# RECEIVER.net
KiCad netlist of a schematic drawn in Altium Designer
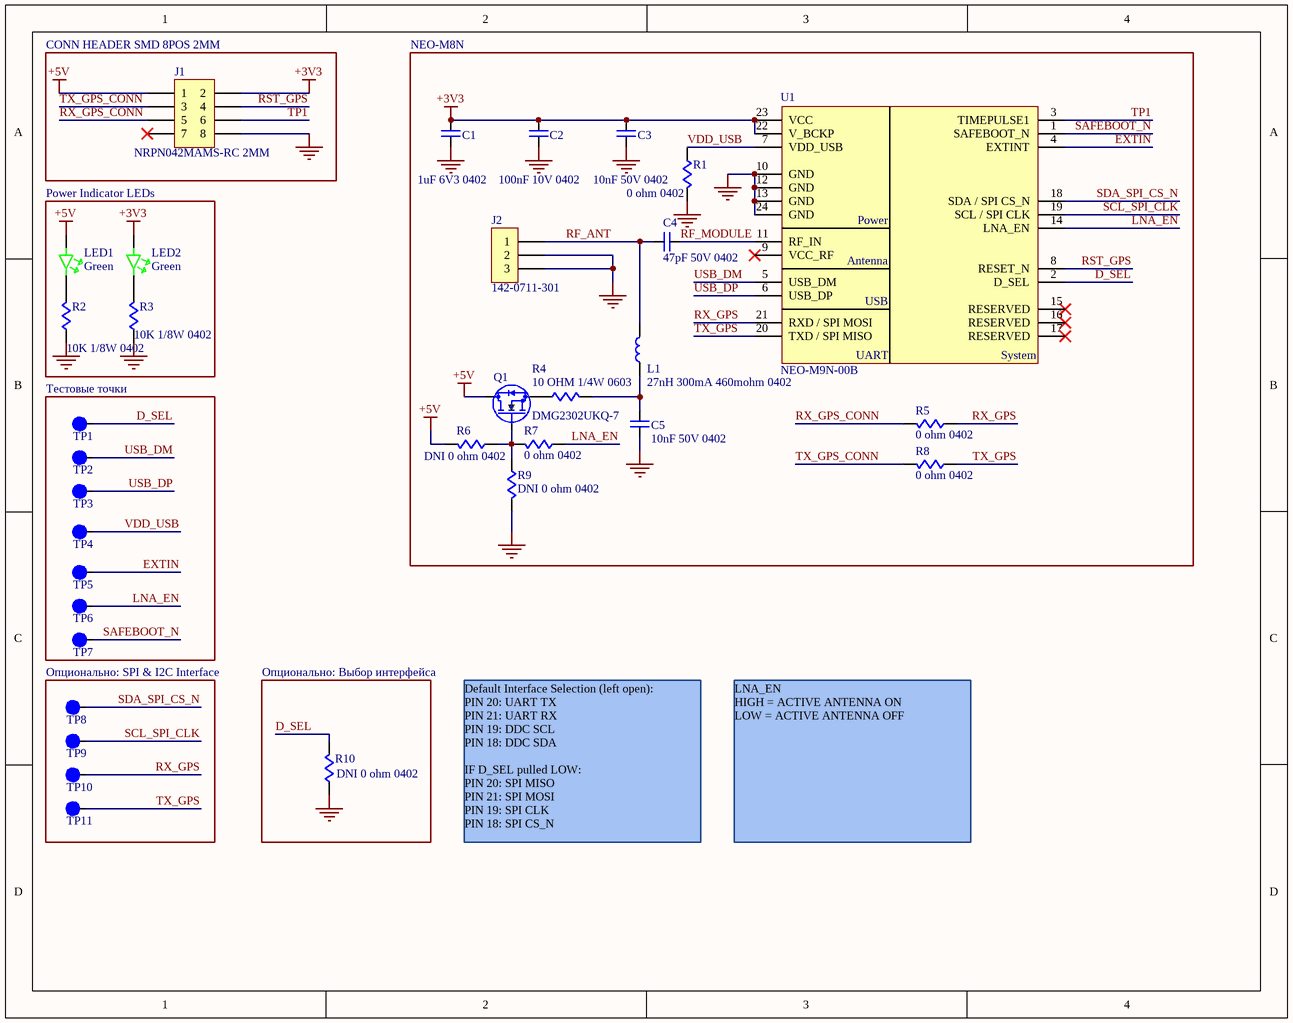
[diagram p0: RECEIVER.SchDoc]

(export (version "E")
  (design (tool "Eeschema 10.0.6"))
  (components
    (comp (ref "C1")
      (value "1uF 6V3 0402")
      (footprint "c0402")
      (description "0402 1 uF 6.3 V ±10% Tolerance X7R Multilayer Ceramic Capacitor")
      (fields
        (field (name "MANUFACTURER") "Murata")
        (field (name "MANUFACTURER PART NUMBER") "GRM155R70J105KA12J")
      )
      (libsource (lib "MyLibrary") (part "CAP CER 1UF 6.3V X7R 0402"))
    )
    (comp (ref "C2")
      (value "100nF 10V 0402")
      (footprint "c0402")
      (description "CL05 Series 0.1 uF 10 V ±10 % Tolerance X7R SMT Multilayer Ceramic Capacitor")
      (fields
        (field (name "MANUFACTURER") "Samsung")
        (field (name "MANUFACTURER PART NUMBER") "CL05B104KP5NNNC")
      )
      (libsource (lib "MyLibrary") (part "CAP CER 0.1UF 10V X7R 0402"))
    )
    (comp (ref "C3")
      (value "10nF 50V 0402")
      (footprint "c0402")
      (description "CAP CER 10000PF 50V X7R 0402")
      (fields
        (field (name "MANUFACTURER") "Murata")
        (field (name "MANUFACTURER PART NUMBER") "GCM155R71H103KA55D")
      )
      (libsource (lib "MyLibrary") (part "CAP CER 10000PF 50V X7R 0402"))
    )
    (comp (ref "C4")
      (value "47pF 50V 0402")
      (footprint "c0402")
      (description "0402 47 pF 50 V ±5 % Tolerance NP0 SMT Multilayer Ceramic Capacitor")
      (fields
        (field (name "MANUFACTURER") "Yageo")
        (field (name "MANUFACTURER PART NUMBER") "CC0402JRNPO9BN470")
      )
      (libsource (lib "MyLibrary") (part "CAP CER 47PF 50V C0G/NPO 0402"))
    )
    (comp (ref "C5")
      (value "10nF 50V 0402")
      (footprint "c0402")
      (description "CAP CER 10000PF 50V X7R 0402")
      (fields
        (field (name "MANUFACTURER") "Murata")
        (field (name "MANUFACTURER PART NUMBER") "GCM155R71H103KA55D")
      )
      (libsource (lib "MyLibrary") (part "CAP CER 10000PF 50V X7R 0402"))
    )
    (comp (ref "J1")
      (value "NRPN042MAMS-RC 2MM")
      (footprint "CONN_NRPN042MAMS-RC")
      (description "Dual Row 8 Position 2 mm Pitch Surface Mount Header")
      (fields
        (field (name "MANUFACTURER") "Sullins")
        (field (name "MANUFACTURER PART NUMBER") "NRPN042MAMS-RC")
      )
      (libsource (lib "MyLibrary") (part "CONN_NRPN042MAMS-RC"))
    )
    (comp (ref "J2")
      (value "142-0711-301")
      (footprint "CONN_131-3711-301")
      (description "Rf Coaxial Board Mount Connector")
      (fields
        (field (name "MANUFACTURER") "Bel Cinch")
        (field (name "MANUFACTURER PART NUMBER") "131-3711-301")
      )
      (libsource (lib "MyLibrary") (part "CONN_131-3711-301"))
    )
    (comp (ref "L1")
      (value "27nH 300mA 460mohm 0402")
      (footprint "L0402")
      (description "Inductor RF Chip Multi-Layer 27nH 5% 100MHz 8Q-Factor Air 300mA 460mOhm DCR 0402 Paper T/R")
      (fields
        (field (name "MANUFACTURER") "Murata")
        (field (name "MANUFACTURER PART NUMBER") "LQG15HS27NJ02D")
      )
      (libsource (lib "MyLibrary") (part "FIXED IND 27NH 350MA 460MOHM SMD"))
    )
    (comp (ref "LED1")
      (value "Green")
      (footprint "led0603")
      (description "LED High-Power Uni-Color Green 574nm 2-Pin Chip LED T/R")
      (fields
        (field (name "MANUFACTURER") "Vishay Lite-On")
        (field (name "MANUFACTURER PART NUMBER") "LTST-C190KGKT")
      )
      (libsource (lib "MyLibrary") (part "LED GREEN CLEAR CHIP SMD"))
    )
    (comp (ref "LED2")
      (value "Green")
      (footprint "led0603")
      (description "LED High-Power Uni-Color Green 574nm 2-Pin Chip LED T/R")
      (fields
        (field (name "MANUFACTURER") "Vishay Lite-On")
        (field (name "MANUFACTURER PART NUMBER") "LTST-C190KGKT")
      )
      (libsource (lib "MyLibrary") (part "LED GREEN CLEAR CHIP SMD"))
    )
    (comp (ref "Q1")
      (value "DMG2302UKQ-7")
      (footprint "SOT23")
      (description "N-Channel 20 V 2.8A (Ta) 660mW (Ta) Surface Mount SOT-23-3")
      (fields
        (field (name "MANUFACTURER") "Diodes")
        (field (name "COPYRIGHT") "Copyright (C) 2022 Ultra Librarian. All rights reserved.")
      )
      (libsource (lib "MyLibrary") (part "DMG2302UKQ-7"))
    )
    (comp (ref "R1")
      (value "0 ohm 0402")
      (footprint "r0402")
      (description "RES SMD 0 OHM JUMPER 1/16W 0402")
      (fields
        (field (name "MANUFACTURER") "Yageo")
        (field (name "MANUFACTURER PART NUMBER") "RC0402JR-070RL")
      )
      (libsource (lib "MyLibrary") (part "RES 0 OHM JUMPER 1/16W 0402"))
    )
    (comp (ref "R2")
      (value "10K 1/8W 0402")
      (footprint "r0402")
      (description "Res Thick Film 0402 10K Ohm 1% 0.125W(1/8W) ±100ppm/°C Pad SMD T/R")
      (fields
        (field (name "MANUFACTURER") "TE Connectivity")
        (field (name "MANUFACTURER PART NUMBER") "CRGP0402F10K")
      )
      (libsource (lib "MyLibrary") (part "RES 10K OHM 1% 1/8W 0402"))
    )
    (comp (ref "R3")
      (value "10K 1/8W 0402")
      (footprint "r0402")
      (description "Res Thick Film 0402 10K Ohm 1% 0.125W(1/8W) ±100ppm/°C Pad SMD T/R")
      (fields
        (field (name "MANUFACTURER") "TE Connectivity")
        (field (name "MANUFACTURER PART NUMBER") "CRGP0402F10K")
      )
      (libsource (lib "MyLibrary") (part "RES 10K OHM 1% 1/8W 0402"))
    )
    (comp (ref "R4")
      (value "10 OHM 1/4W 0603")
      (footprint "r0603")
      (description "Res Surge Chip Thick Film 0603 10 Ohm 1% 1/4W ±200ppm/°C Molded Paper T/R")
      (fields
        (field (name "MANUFACTURER") "Yageo")
        (field (name "MANUFACTURER PART NUMBER") "SR0603FR-7T10RL")
      )
      (libsource (lib "MyLibrary") (part "RES SMD 10 OHM 1% 1/4W 0603"))
    )
    (comp (ref "R5")
      (value "0 ohm 0402")
      (footprint "r0402")
      (description "RES SMD 0 OHM JUMPER 1/16W 0402")
      (fields
        (field (name "MANUFACTURER") "Yageo")
        (field (name "MANUFACTURER PART NUMBER") "RC0402JR-070RL")
      )
      (libsource (lib "MyLibrary") (part "RES 0 OHM JUMPER 1/16W 0402"))
    )
    (comp (ref "R6")
      (value "DNI 0 ohm 0402")
      (footprint "r0402")
      (description "RES SMD 0 OHM JUMPER 1/16W 0402")
      (fields
        (field (name "MANUFACTURER") "Yageo")
        (field (name "MANUFACTURER PART NUMBER") "RC0402JR-070RL")
      )
      (libsource (lib "MyLibrary") (part "RES 0 OHM JUMPER 1/16W 0402"))
    )
    (comp (ref "R7")
      (value "0 ohm 0402")
      (footprint "r0402")
      (description "RES SMD 0 OHM JUMPER 1/16W 0402")
      (fields
        (field (name "MANUFACTURER") "Yageo")
        (field (name "MANUFACTURER PART NUMBER") "RC0402JR-070RL")
      )
      (libsource (lib "MyLibrary") (part "RES 0 OHM JUMPER 1/16W 0402"))
    )
    (comp (ref "R8")
      (value "0 ohm 0402")
      (footprint "r0402")
      (description "RES SMD 0 OHM JUMPER 1/16W 0402")
      (fields
        (field (name "MANUFACTURER") "Yageo")
        (field (name "MANUFACTURER PART NUMBER") "RC0402JR-070RL")
      )
      (libsource (lib "MyLibrary") (part "RES 0 OHM JUMPER 1/16W 0402"))
    )
    (comp (ref "R9")
      (value "DNI 0 ohm 0402")
      (footprint "r0402")
      (description "RES SMD 0 OHM JUMPER 1/16W 0402")
      (fields
        (field (name "MANUFACTURER") "Yageo")
        (field (name "MANUFACTURER PART NUMBER") "RC0402JR-070RL")
      )
      (libsource (lib "MyLibrary") (part "RES 0 OHM JUMPER 1/16W 0402"))
    )
    (comp (ref "R10")
      (value "DNI 0 ohm 0402")
      (footprint "r0402")
      (description "RES SMD 0 OHM JUMPER 1/16W 0402")
      (fields
        (field (name "MANUFACTURER") "Yageo")
        (field (name "MANUFACTURER PART NUMBER") "RC0402JR-070RL")
      )
      (libsource (lib "MyLibrary") (part "RES 0 OHM JUMPER 1/16W 0402"))
    )
    (comp (ref "TP1")
      (value "1MM")
      (footprint "TP1MM")
      (description "Test Point 1MM diameter")
      (libsource (lib "MyLibrary") (part "TP_1MM"))
    )
    (comp (ref "TP2")
      (value "1MM")
      (footprint "TP1MM")
      (description "Test Point 1MM diameter")
      (libsource (lib "MyLibrary") (part "TP_1MM"))
    )
    (comp (ref "TP3")
      (value "1MM")
      (footprint "TP1MM")
      (description "Test Point 1MM diameter")
      (libsource (lib "MyLibrary") (part "TP_1MM"))
    )
    (comp (ref "TP4")
      (value "1MM")
      (footprint "TP1MM")
      (description "Test Point 1MM diameter")
      (libsource (lib "MyLibrary") (part "TP_1MM"))
    )
    (comp (ref "TP5")
      (value "1MM")
      (footprint "TP1MM")
      (description "Test Point 1MM diameter")
      (libsource (lib "MyLibrary") (part "TP_1MM"))
    )
    (comp (ref "TP6")
      (value "1MM")
      (footprint "TP1MM")
      (description "Test Point 1MM diameter")
      (libsource (lib "MyLibrary") (part "TP_1MM"))
    )
    (comp (ref "TP7")
      (value "1MM")
      (footprint "TP1MM")
      (description "Test Point 1MM diameter")
      (libsource (lib "MyLibrary") (part "TP_1MM"))
    )
    (comp (ref "TP8")
      (value "1MM")
      (footprint "TP1MM")
      (description "Test Point 1MM diameter")
      (libsource (lib "MyLibrary") (part "TP_1MM"))
    )
    (comp (ref "TP9")
      (value "1MM")
      (footprint "TP1MM")
      (description "Test Point 1MM diameter")
      (libsource (lib "MyLibrary") (part "TP_1MM"))
    )
    (comp (ref "TP10")
      (value "1MM")
      (footprint "TP1MM")
      (description "Test Point 1MM diameter")
      (libsource (lib "MyLibrary") (part "TP_1MM"))
    )
    (comp (ref "TP11")
      (value "1MM")
      (footprint "TP1MM")
      (description "Test Point 1MM diameter")
      (libsource (lib "MyLibrary") (part "TP_1MM"))
    )
    (comp (ref "U1")
      (value "NEO-M9N-00B")
      (footprint "IC_NEO-M9N")
      (description "GNSS module, Flash, TCXO, SAW, LNA, LCC, 12x16 mm Professional Grade")
      (fields (field (name "MANUFACTURER") "u-blox"))
      (libsource (lib "MyLibrary") (part "IC NEO-M9N-00B"))
    )
  )
  (nets
    (net (code "1") (name "+3V3") (class "Default")
      (node (ref "C1") (pin "2") (pinfunction "2_2") (pintype "passive"))
      (node (ref "C2") (pin "2") (pinfunction "2_2") (pintype "passive"))
      (node (ref "C3") (pin "2") (pinfunction "2_2") (pintype "passive"))
      (node (ref "J1") (pin "2") (pinfunction "2_2") (pintype "passive"))
      (node (ref "LED2") (pin "1") (pinfunction "1_1") (pintype "passive"))
      (node (ref "U1") (pin "22") (pinfunction "V_BCKP_22") (pintype "passive"))
      (node (ref "U1") (pin "23") (pinfunction "VCC_23") (pintype "passive"))
    )
    (net (code "2") (name "+5V") (class "Default")
      (node (ref "J1") (pin "1") (pinfunction "1_1") (pintype "passive"))
      (node (ref "LED1") (pin "1") (pinfunction "1_1") (pintype "passive"))
      (node (ref "Q1") (pin "2") (pinfunction "D_2") (pintype "passive"))
      (node (ref "R6") (pin "2") (pinfunction "2_2") (pintype "passive"))
    )
    (net (code "3") (name "/D_SEL") (class "Default")
      (node (ref "R10") (pin "2") (pinfunction "2_2") (pintype "passive"))
      (node (ref "TP1") (pin "1") (pinfunction "1_1") (pintype "passive"))
      (node (ref "U1") (pin "2") (pinfunction "D_SEL_2") (pintype "passive"))
    )
    (net (code "4") (name "/EXTIN") (class "Default")
      (node (ref "TP5") (pin "1") (pinfunction "1_1") (pintype "passive"))
      (node (ref "U1") (pin "4") (pinfunction "EXTINT_4") (pintype "passive"))
    )
    (net (code "5") (name "/LNA_EN") (class "Default")
      (node (ref "R7") (pin "1") (pinfunction "1_1") (pintype "passive"))
      (node (ref "TP6") (pin "1") (pinfunction "1_1") (pintype "passive"))
      (node (ref "U1") (pin "14") (pinfunction "LNA_EN_14") (pintype "passive"))
    )
    (net (code "6") (name "/RF_ANT") (class "Default")
      (node (ref "C4") (pin "1") (pinfunction "1_1") (pintype "passive"))
      (node (ref "J2") (pin "1") (pinfunction "1_1") (pintype "passive"))
      (node (ref "L1") (pin "2") (pinfunction "2_2") (pintype "passive"))
    )
    (net (code "7") (name "/RF_MODULE") (class "Default")
      (node (ref "C4") (pin "2") (pinfunction "2_2") (pintype "passive"))
      (node (ref "U1") (pin "11") (pinfunction "RF_IN_11") (pintype "passive"))
    )
    (net (code "8") (name "/RST_GPS") (class "Default")
      (node (ref "J1") (pin "4") (pinfunction "4_4") (pintype "passive"))
      (node (ref "U1") (pin "8") (pinfunction "RESET_N_8") (pintype "passive"))
    )
    (net (code "9") (name "/RX_GPS") (class "Default")
      (node (ref "R5") (pin "1") (pinfunction "1_1") (pintype "passive"))
      (node (ref "TP10") (pin "1") (pinfunction "1_1") (pintype "passive"))
      (node (ref "U1") (pin "21") (pinfunction "RXD_/_SPI_MOSI_21") (pintype "passive"))
    )
    (net (code "10") (name "/RX_GPS_CONN") (class "Default")
      (node (ref "J1") (pin "5") (pinfunction "5_5") (pintype "passive"))
      (node (ref "R5") (pin "2") (pinfunction "2_2") (pintype "passive"))
    )
    (net (code "11") (name "/SAFEBOOT_N") (class "Default")
      (node (ref "TP7") (pin "1") (pinfunction "1_1") (pintype "passive"))
      (node (ref "U1") (pin "1") (pinfunction "SAFEBOOT_N_1") (pintype "passive"))
    )
    (net (code "12") (name "/SCL_SPI_CLK") (class "Default")
      (node (ref "TP9") (pin "1") (pinfunction "1_1") (pintype "passive"))
      (node (ref "U1") (pin "19") (pinfunction "SCL_/_SPI_CLK_19") (pintype "passive"))
    )
    (net (code "13") (name "/SDA_SPI_CS_N") (class "Default")
      (node (ref "TP8") (pin "1") (pinfunction "1_1") (pintype "passive"))
      (node (ref "U1") (pin "18") (pinfunction "SDA_/_SPI_CS_N_18") (pintype "passive"))
    )
    (net (code "14") (name "/TP1") (class "Default")
      (node (ref "J1") (pin "6") (pinfunction "6_6") (pintype "passive"))
      (node (ref "U1") (pin "3") (pinfunction "TIMEPULSE1_3") (pintype "passive"))
    )
    (net (code "15") (name "/TX_GPS") (class "Default")
      (node (ref "R8") (pin "1") (pinfunction "1_1") (pintype "passive"))
      (node (ref "TP11") (pin "1") (pinfunction "1_1") (pintype "passive"))
      (node (ref "U1") (pin "20") (pinfunction "TXD_/_SPI_MISO_20") (pintype "passive"))
    )
    (net (code "16") (name "/TX_GPS_CONN") (class "Default")
      (node (ref "J1") (pin "3") (pinfunction "3_3") (pintype "passive"))
      (node (ref "R8") (pin "2") (pinfunction "2_2") (pintype "passive"))
    )
    (net (code "17") (name "/USB_DM") (class "Default")
      (node (ref "TP2") (pin "1") (pinfunction "1_1") (pintype "passive"))
      (node (ref "U1") (pin "5") (pinfunction "USB_DM_5") (pintype "passive"))
    )
    (net (code "18") (name "/USB_DP") (class "Default")
      (node (ref "TP3") (pin "1") (pinfunction "1_1") (pintype "passive"))
      (node (ref "U1") (pin "6") (pinfunction "USB_DP_6") (pintype "passive"))
    )
    (net (code "19") (name "/VDD_USB") (class "Default")
      (node (ref "R1") (pin "1") (pinfunction "1_1") (pintype "passive"))
      (node (ref "TP4") (pin "1") (pinfunction "1_1") (pintype "passive"))
      (node (ref "U1") (pin "7") (pinfunction "VDD_USB_7") (pintype "passive"))
    )
    (net (code "20") (name "GND") (class "Default")
      (node (ref "C1") (pin "1") (pinfunction "1_1") (pintype "passive"))
      (node (ref "C2") (pin "1") (pinfunction "1_1") (pintype "passive"))
      (node (ref "C3") (pin "1") (pinfunction "1_1") (pintype "passive"))
      (node (ref "C5") (pin "1") (pinfunction "1_1") (pintype "passive"))
      (node (ref "J1") (pin "8") (pinfunction "8_8") (pintype "passive"))
      (node (ref "J2") (pin "2") (pinfunction "2_2") (pintype "passive"))
      (node (ref "J2") (pin "3") (pinfunction "3_3") (pintype "passive"))
      (node (ref "R1") (pin "2") (pinfunction "2_2") (pintype "passive"))
      (node (ref "R10") (pin "1") (pinfunction "1_1") (pintype "passive"))
      (node (ref "R2") (pin "1") (pinfunction "1_1") (pintype "passive"))
      (node (ref "R3") (pin "1") (pinfunction "1_1") (pintype "passive"))
      (node (ref "R9") (pin "2") (pinfunction "2_2") (pintype "passive"))
      (node (ref "U1") (pin "10") (pinfunction "GND_10") (pintype "passive"))
      (node (ref "U1") (pin "12") (pinfunction "GND_12") (pintype "passive"))
      (node (ref "U1") (pin "13") (pinfunction "GND_13") (pintype "passive"))
      (node (ref "U1") (pin "24") (pinfunction "GND_24") (pintype "passive"))
    )
    (net (code "21") (name "Net-(C5-Pad2)") (class "Default")
      (node (ref "C5") (pin "2") (pinfunction "2_2") (pintype "passive"))
      (node (ref "L1") (pin "1") (pinfunction "1_1") (pintype "passive"))
      (node (ref "R4") (pin "2") (pinfunction "2_2") (pintype "passive"))
    )
    (net (code "22") (name "Net-(LED1-Pad2)") (class "Default")
      (node (ref "LED1") (pin "2") (pinfunction "2_2") (pintype "passive"))
      (node (ref "R2") (pin "2") (pinfunction "2_2") (pintype "passive"))
    )
    (net (code "23") (name "Net-(LED2-Pad2)") (class "Default")
      (node (ref "LED2") (pin "2") (pinfunction "2_2") (pintype "passive"))
      (node (ref "R3") (pin "2") (pinfunction "2_2") (pintype "passive"))
    )
    (net (code "24") (name "Net-(Q1-G)") (class "Default")
      (node (ref "Q1") (pin "1") (pinfunction "G_1") (pintype "passive"))
      (node (ref "R6") (pin "1") (pinfunction "1_1") (pintype "passive"))
      (node (ref "R7") (pin "2") (pinfunction "2_2") (pintype "passive"))
      (node (ref "R9") (pin "1") (pinfunction "1_1") (pintype "passive"))
    )
    (net (code "25") (name "Net-(Q1-S)") (class "Default")
      (node (ref "Q1") (pin "3") (pinfunction "S_3") (pintype "passive"))
      (node (ref "R4") (pin "1") (pinfunction "1_1") (pintype "passive"))
    )
    (net (code "26") (name "unconnected-(J1-Pad7)") (class "Default")
      (node (ref "J1") (pin "7") (pinfunction "7_7") (pintype "passive+no_connect"))
    )
    (net (code "27") (name "unconnected-(U1-RESERVED-Pad15)") (class "Default")
      (node (ref "U1") (pin "15") (pinfunction "RESERVED_15") (pintype "passive+no_connect"))
    )
    (net (code "28") (name "unconnected-(U1-RESERVED-Pad16)") (class "Default")
      (node (ref "U1") (pin "16") (pinfunction "RESERVED_16") (pintype "passive+no_connect"))
    )
    (net (code "29") (name "unconnected-(U1-RESERVED-Pad17)") (class "Default")
      (node (ref "U1") (pin "17") (pinfunction "RESERVED_17") (pintype "passive+no_connect"))
    )
    (net (code "30") (name "unconnected-(U1-VCC_RF-Pad9)") (class "Default")
      (node (ref "U1") (pin "9") (pinfunction "VCC_RF_9") (pintype "passive+no_connect"))
    )
  )
)
